# high.net
KiCad netlist of a schematic drawn in Altium Designer
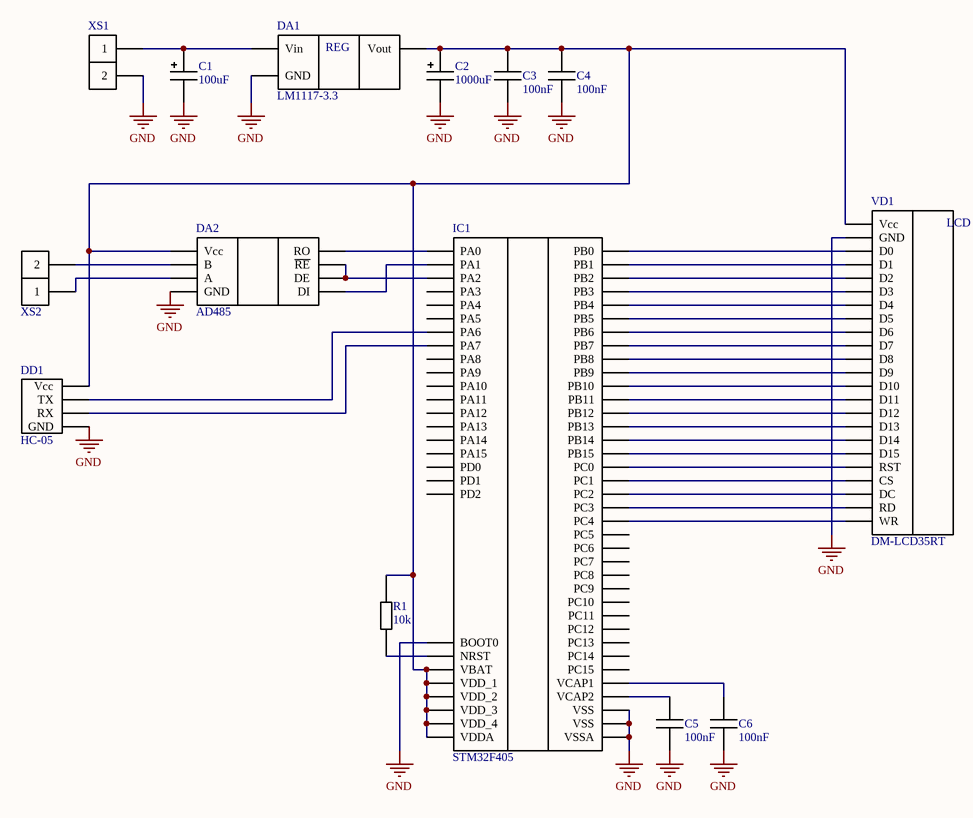
[diagram p0: high.SchDoc]

(export (version "E")
  (design (tool "Eeschema 10.0.6"))
  (components
    (comp (ref "C1") (value "100uF") (libsource (lib "EDDLib") (part "CAP_POLAR")))
    (comp (ref "C2") (value "1000uF") (libsource (lib "EDDLib") (part "CAP_POLAR")))
    (comp (ref "C3") (value "100nF") (libsource (lib "EDDLib") (part "CAP_NONPOLAR")))
    (comp (ref "C4") (value "100nF") (libsource (lib "EDDLib") (part "CAP_NONPOLAR")))
    (comp (ref "C5") (value "100nF") (libsource (lib "EDDLib") (part "CAP_NONPOLAR")))
    (comp (ref "C6") (value "100nF") (libsource (lib "EDDLib") (part "CAP_NONPOLAR")))
    (comp (ref "DA1") (value "LM1117-3.3") (libsource (lib "EDDLib") (part "LM1117-3.3")))
    (comp (ref "DA2") (value "AD485") (libsource (lib "EDDLib") (part "AD485")))
    (comp (ref "DD1") (value "HC-05") (libsource (lib "EDDLib") (part "BT")))
    (comp (ref "IC1")
      (value "STM32F405")
      (description "STM32 ARM-based 32-bit MCU")
      (libsource (lib "EDDLib") (part "STM32F405"))
    )
    (comp (ref "R1") (value "10k") (libsource (lib "EDDLib") (part "RES")))
    (comp (ref "VD1") (value "DM-LCD35RT") (libsource (lib "EDDLib") (part "LCD")))
    (comp (ref "XS1") (value "CONN-2") (libsource (lib "EDDLib") (part "CONN-2")))
    (comp (ref "XS2") (value "CONN-2") (libsource (lib "EDDLib") (part "CONN-2")))
  )
  (nets
    (net (code "1") (name "GND") (class "Default")
      (node (ref "C1") (pin "2") (pinfunction "2_2") (pintype "passive"))
      (node (ref "C2") (pin "2") (pinfunction "2_2") (pintype "passive"))
      (node (ref "C3") (pin "2") (pinfunction "2_2") (pintype "passive"))
      (node (ref "C4") (pin "2") (pinfunction "2_2") (pintype "passive"))
      (node (ref "C5") (pin "2") (pinfunction "2_2") (pintype "passive"))
      (node (ref "C6") (pin "2") (pinfunction "2_2") (pintype "passive"))
      (node (ref "DA1") (pin "3") (pinfunction "GND_3") (pintype "passive"))
      (node (ref "DA2") (pin "5") (pinfunction "GND_5") (pintype "passive"))
      (node (ref "DD1") (pin "5") (pinfunction "GND_5") (pintype "passive"))
      (node (ref "IC1") (pin "12") (pinfunction "VSSA_12") (pintype "passive"))
      (node (ref "IC1") (pin "18") (pinfunction "VSS_18") (pintype "passive"))
      (node (ref "IC1") (pin "60") (pinfunction "BOOT0_60") (pintype "passive"))
      (node (ref "IC1") (pin "63") (pinfunction "VSS_63") (pintype "passive"))
      (node (ref "VD1") (pin "16") (pinfunction "GND_16") (pintype "passive"))
      (node (ref "XS1") (pin "2") (pinfunction "2_2") (pintype "passive"))
    )
    (net (code "2") (name "Net-(DA1-Vin)") (class "Default")
      (node (ref "C1") (pin "1") (pinfunction "1_1") (pintype "passive"))
      (node (ref "DA1") (pin "1") (pinfunction "Vin_1") (pintype "passive"))
      (node (ref "XS1") (pin "1") (pinfunction "1_1") (pintype "passive"))
    )
    (net (code "3") (name "Net-(DA1-Vout)") (class "Default")
      (node (ref "C2") (pin "1") (pinfunction "1_1") (pintype "passive"))
      (node (ref "C3") (pin "1") (pinfunction "1_1") (pintype "passive"))
      (node (ref "C4") (pin "1") (pinfunction "1_1") (pintype "passive"))
      (node (ref "DA1") (pin "2") (pinfunction "Vout_2") (pintype "passive"))
      (node (ref "DA2") (pin "8") (pinfunction "Vcc_8") (pintype "passive"))
      (node (ref "DD1") (pin "8") (pinfunction "Vcc_8") (pintype "passive"))
      (node (ref "IC1") (pin "1") (pinfunction "VBAT_1") (pintype "passive"))
      (node (ref "IC1") (pin "13") (pinfunction "VDDA_13") (pintype "passive"))
      (node (ref "IC1") (pin "19") (pinfunction "VDD_4_19") (pintype "passive"))
      (node (ref "IC1") (pin "32") (pinfunction "VDD_1_32") (pintype "passive"))
      (node (ref "IC1") (pin "48") (pinfunction "VDD_2_48") (pintype "passive"))
      (node (ref "IC1") (pin "64") (pinfunction "VDD_3_64") (pintype "passive"))
      (node (ref "R1") (pin "1") (pinfunction "1_1") (pintype "passive"))
      (node (ref "VD1") (pin "15") (pinfunction "Vcc_15") (pintype "passive"))
    )
    (net (code "4") (name "Net-(DA2-A)") (class "Default")
      (node (ref "DA2") (pin "6") (pinfunction "A_6") (pintype "passive"))
      (node (ref "XS2") (pin "1") (pinfunction "1_1") (pintype "passive"))
    )
    (net (code "5") (name "Net-(DA2-B)") (class "Default")
      (node (ref "DA2") (pin "7") (pinfunction "B_7") (pintype "passive"))
      (node (ref "XS2") (pin "2") (pinfunction "2_2") (pintype "passive"))
    )
    (net (code "6") (name "Net-(DA2-DE)") (class "Default")
      (node (ref "DA2") (pin "2") (pinfunction "~{RE}_2") (pintype "passive"))
      (node (ref "DA2") (pin "3") (pinfunction "DE_3") (pintype "passive"))
      (node (ref "IC1") (pin "16") (pinfunction "PA2_16") (pintype "passive"))
    )
    (net (code "7") (name "Net-(DA2-DI)") (class "Default")
      (node (ref "DA2") (pin "4") (pinfunction "DI_4") (pintype "passive"))
      (node (ref "IC1") (pin "15") (pinfunction "PA1_15") (pintype "passive"))
    )
    (net (code "8") (name "Net-(DA2-RO)") (class "Default")
      (node (ref "DA2") (pin "1") (pinfunction "RO_1") (pintype "passive"))
      (node (ref "IC1") (pin "14") (pinfunction "PA0_14") (pintype "passive"))
    )
    (net (code "9") (name "Net-(DD1-RX)") (class "Default")
      (node (ref "DD1") (pin "6") (pinfunction "RX_6") (pintype "passive"))
      (node (ref "IC1") (pin "23") (pinfunction "PA7_23") (pintype "passive"))
    )
    (net (code "10") (name "Net-(DD1-TX)") (class "Default")
      (node (ref "DD1") (pin "7") (pinfunction "TX_7") (pintype "passive"))
      (node (ref "IC1") (pin "22") (pinfunction "PA6_22") (pintype "passive"))
    )
    (net (code "11") (name "Net-(IC1-NRST)") (class "Default")
      (node (ref "IC1") (pin "7") (pinfunction "NRST_7") (pintype "passive"))
      (node (ref "R1") (pin "2") (pinfunction "2_2") (pintype "passive"))
    )
    (net (code "12") (name "Net-(IC1-PB0)") (class "Default")
      (node (ref "IC1") (pin "26") (pinfunction "PB0_26") (pintype "passive"))
      (node (ref "VD1") (pin "17") (pinfunction "D0_17") (pintype "passive"))
    )
    (net (code "13") (name "Net-(IC1-PB1)") (class "Default")
      (node (ref "IC1") (pin "27") (pinfunction "PB1_27") (pintype "passive"))
      (node (ref "VD1") (pin "18") (pinfunction "D1_18") (pintype "passive"))
    )
    (net (code "14") (name "Net-(IC1-PB2)") (class "Default")
      (node (ref "IC1") (pin "28") (pinfunction "PB2_28") (pintype "passive"))
      (node (ref "VD1") (pin "19") (pinfunction "D2_19") (pintype "passive"))
    )
    (net (code "15") (name "Net-(IC1-PB3)") (class "Default")
      (node (ref "IC1") (pin "55") (pinfunction "PB3_55") (pintype "passive"))
      (node (ref "VD1") (pin "20") (pinfunction "D3_20") (pintype "passive"))
    )
    (net (code "16") (name "Net-(IC1-PB4)") (class "Default")
      (node (ref "IC1") (pin "56") (pinfunction "PB4_56") (pintype "passive"))
      (node (ref "VD1") (pin "21") (pinfunction "D4_21") (pintype "passive"))
    )
    (net (code "17") (name "Net-(IC1-PB5)") (class "Default")
      (node (ref "IC1") (pin "57") (pinfunction "PB5_57") (pintype "passive"))
      (node (ref "VD1") (pin "22") (pinfunction "D5_22") (pintype "passive"))
    )
    (net (code "18") (name "Net-(IC1-PB6)") (class "Default")
      (node (ref "IC1") (pin "58") (pinfunction "PB6_58") (pintype "passive"))
      (node (ref "VD1") (pin "23") (pinfunction "D6_23") (pintype "passive"))
    )
    (net (code "19") (name "Net-(IC1-PB7)") (class "Default")
      (node (ref "IC1") (pin "59") (pinfunction "PB7_59") (pintype "passive"))
      (node (ref "VD1") (pin "24") (pinfunction "D7_24") (pintype "passive"))
    )
    (net (code "20") (name "Net-(IC1-PB8)") (class "Default")
      (node (ref "IC1") (pin "61") (pinfunction "PB8_61") (pintype "passive"))
      (node (ref "VD1") (pin "25") (pinfunction "D8_25") (pintype "passive"))
    )
    (net (code "21") (name "Net-(IC1-PB9)") (class "Default")
      (node (ref "IC1") (pin "62") (pinfunction "PB9_62") (pintype "passive"))
      (node (ref "VD1") (pin "26") (pinfunction "D9_26") (pintype "passive"))
    )
    (net (code "22") (name "Net-(IC1-PB10)") (class "Default")
      (node (ref "IC1") (pin "29") (pinfunction "PB10_29") (pintype "passive"))
      (node (ref "VD1") (pin "27") (pinfunction "D10_27") (pintype "passive"))
    )
    (net (code "23") (name "Net-(IC1-PB11)") (class "Default")
      (node (ref "IC1") (pin "30") (pinfunction "PB11_30") (pintype "passive"))
      (node (ref "VD1") (pin "28") (pinfunction "D11_28") (pintype "passive"))
    )
    (net (code "24") (name "Net-(IC1-PB12)") (class "Default")
      (node (ref "IC1") (pin "33") (pinfunction "PB12_33") (pintype "passive"))
      (node (ref "VD1") (pin "29") (pinfunction "D12_29") (pintype "passive"))
    )
    (net (code "25") (name "Net-(IC1-PB13)") (class "Default")
      (node (ref "IC1") (pin "34") (pinfunction "PB13_34") (pintype "passive"))
      (node (ref "VD1") (pin "30") (pinfunction "D13_30") (pintype "passive"))
    )
    (net (code "26") (name "Net-(IC1-PB14)") (class "Default")
      (node (ref "IC1") (pin "35") (pinfunction "PB14_35") (pintype "passive"))
      (node (ref "VD1") (pin "31") (pinfunction "D14_31") (pintype "passive"))
    )
    (net (code "27") (name "Net-(IC1-PB15)") (class "Default")
      (node (ref "IC1") (pin "36") (pinfunction "PB15_36") (pintype "passive"))
      (node (ref "VD1") (pin "32") (pinfunction "D15_32") (pintype "passive"))
    )
    (net (code "28") (name "Net-(IC1-PC0)") (class "Default")
      (node (ref "IC1") (pin "8") (pinfunction "PC0_8") (pintype "passive"))
      (node (ref "VD1") (pin "34") (pinfunction "RST_34") (pintype "passive"))
    )
    (net (code "29") (name "Net-(IC1-PC1)") (class "Default")
      (node (ref "IC1") (pin "9") (pinfunction "PC1_9") (pintype "passive"))
      (node (ref "VD1") (pin "35") (pinfunction "CS_35") (pintype "passive"))
    )
    (net (code "30") (name "Net-(IC1-PC2)") (class "Default")
      (node (ref "IC1") (pin "10") (pinfunction "PC2_10") (pintype "passive"))
      (node (ref "VD1") (pin "36") (pinfunction "DC_36") (pintype "passive"))
    )
    (net (code "31") (name "Net-(IC1-PC3)") (class "Default")
      (node (ref "IC1") (pin "11") (pinfunction "PC3_11") (pintype "passive"))
      (node (ref "VD1") (pin "37") (pinfunction "RD_37") (pintype "passive"))
    )
    (net (code "32") (name "Net-(IC1-PC4)") (class "Default")
      (node (ref "IC1") (pin "24") (pinfunction "PC4_24") (pintype "passive"))
      (node (ref "VD1") (pin "38") (pinfunction "WR_38") (pintype "passive"))
    )
    (net (code "33") (name "Net-(IC1-VCAP1)") (class "Default")
      (node (ref "C6") (pin "1") (pinfunction "1_1") (pintype "passive"))
      (node (ref "IC1") (pin "31") (pinfunction "VCAP1_31") (pintype "passive"))
    )
    (net (code "34") (name "Net-(IC1-VCAP2)") (class "Default")
      (node (ref "C5") (pin "1") (pinfunction "1_1") (pintype "passive"))
      (node (ref "IC1") (pin "47") (pinfunction "VCAP2_47") (pintype "passive"))
    )
    (net (code "35") (name "unconnected-(IC1-PA3-Pad17)") (class "Default")
      (node (ref "IC1") (pin "17") (pinfunction "PA3_17") (pintype "passive"))
    )
    (net (code "36") (name "unconnected-(IC1-PA4-Pad20)") (class "Default")
      (node (ref "IC1") (pin "20") (pinfunction "PA4_20") (pintype "passive"))
    )
    (net (code "37") (name "unconnected-(IC1-PA5-Pad21)") (class "Default")
      (node (ref "IC1") (pin "21") (pinfunction "PA5_21") (pintype "passive"))
    )
    (net (code "38") (name "unconnected-(IC1-PA8-Pad41)") (class "Default")
      (node (ref "IC1") (pin "41") (pinfunction "PA8_41") (pintype "passive"))
    )
    (net (code "39") (name "unconnected-(IC1-PA9-Pad42)") (class "Default")
      (node (ref "IC1") (pin "42") (pinfunction "PA9_42") (pintype "passive"))
    )
    (net (code "40") (name "unconnected-(IC1-PA10-Pad43)") (class "Default")
      (node (ref "IC1") (pin "43") (pinfunction "PA10_43") (pintype "passive"))
    )
    (net (code "41") (name "unconnected-(IC1-PA11-Pad44)") (class "Default")
      (node (ref "IC1") (pin "44") (pinfunction "PA11_44") (pintype "passive"))
    )
    (net (code "42") (name "unconnected-(IC1-PA12-Pad45)") (class "Default")
      (node (ref "IC1") (pin "45") (pinfunction "PA12_45") (pintype "passive"))
    )
    (net (code "43") (name "unconnected-(IC1-PA13-Pad46)") (class "Default")
      (node (ref "IC1") (pin "46") (pinfunction "PA13_46") (pintype "passive"))
    )
    (net (code "44") (name "unconnected-(IC1-PA14-Pad49)") (class "Default")
      (node (ref "IC1") (pin "49") (pinfunction "PA14_49") (pintype "passive"))
    )
    (net (code "45") (name "unconnected-(IC1-PA15-Pad50)") (class "Default")
      (node (ref "IC1") (pin "50") (pinfunction "PA15_50") (pintype "passive"))
    )
    (net (code "46") (name "unconnected-(IC1-PC5-Pad25)") (class "Default")
      (node (ref "IC1") (pin "25") (pinfunction "PC5_25") (pintype "passive"))
    )
    (net (code "47") (name "unconnected-(IC1-PC6-Pad37)") (class "Default")
      (node (ref "IC1") (pin "37") (pinfunction "PC6_37") (pintype "passive"))
    )
    (net (code "48") (name "unconnected-(IC1-PC7-Pad38)") (class "Default")
      (node (ref "IC1") (pin "38") (pinfunction "PC7_38") (pintype "passive"))
    )
    (net (code "49") (name "unconnected-(IC1-PC8-Pad39)") (class "Default")
      (node (ref "IC1") (pin "39") (pinfunction "PC8_39") (pintype "passive"))
    )
    (net (code "50") (name "unconnected-(IC1-PC9-Pad40)") (class "Default")
      (node (ref "IC1") (pin "40") (pinfunction "PC9_40") (pintype "passive"))
    )
    (net (code "51") (name "unconnected-(IC1-PC10-Pad51)") (class "Default")
      (node (ref "IC1") (pin "51") (pinfunction "PC10_51") (pintype "passive"))
    )
    (net (code "52") (name "unconnected-(IC1-PC11-Pad52)") (class "Default")
      (node (ref "IC1") (pin "52") (pinfunction "PC11_52") (pintype "passive"))
    )
    (net (code "53") (name "unconnected-(IC1-PC12-Pad53)") (class "Default")
      (node (ref "IC1") (pin "53") (pinfunction "PC12_53") (pintype "passive"))
    )
    (net (code "54") (name "unconnected-(IC1-PC13-Pad2)") (class "Default")
      (node (ref "IC1") (pin "2") (pinfunction "PC13_2") (pintype "passive"))
    )
    (net (code "55") (name "unconnected-(IC1-PC14-Pad3)") (class "Default")
      (node (ref "IC1") (pin "3") (pinfunction "PC14_3") (pintype "passive"))
    )
    (net (code "56") (name "unconnected-(IC1-PC15-Pad4)") (class "Default")
      (node (ref "IC1") (pin "4") (pinfunction "PC15_4") (pintype "passive"))
    )
    (net (code "57") (name "unconnected-(IC1-PD0-Pad5)") (class "Default")
      (node (ref "IC1") (pin "5") (pinfunction "PD0_5") (pintype "passive"))
    )
    (net (code "58") (name "unconnected-(IC1-PD1-Pad6)") (class "Default")
      (node (ref "IC1") (pin "6") (pinfunction "PD1_6") (pintype "passive"))
    )
    (net (code "59") (name "unconnected-(IC1-PD2-Pad54)") (class "Default")
      (node (ref "IC1") (pin "54") (pinfunction "PD2_54") (pintype "passive"))
    )
  )
)
